# bm20_breakout.net
KiCad netlist of a schematic drawn in EAGLE
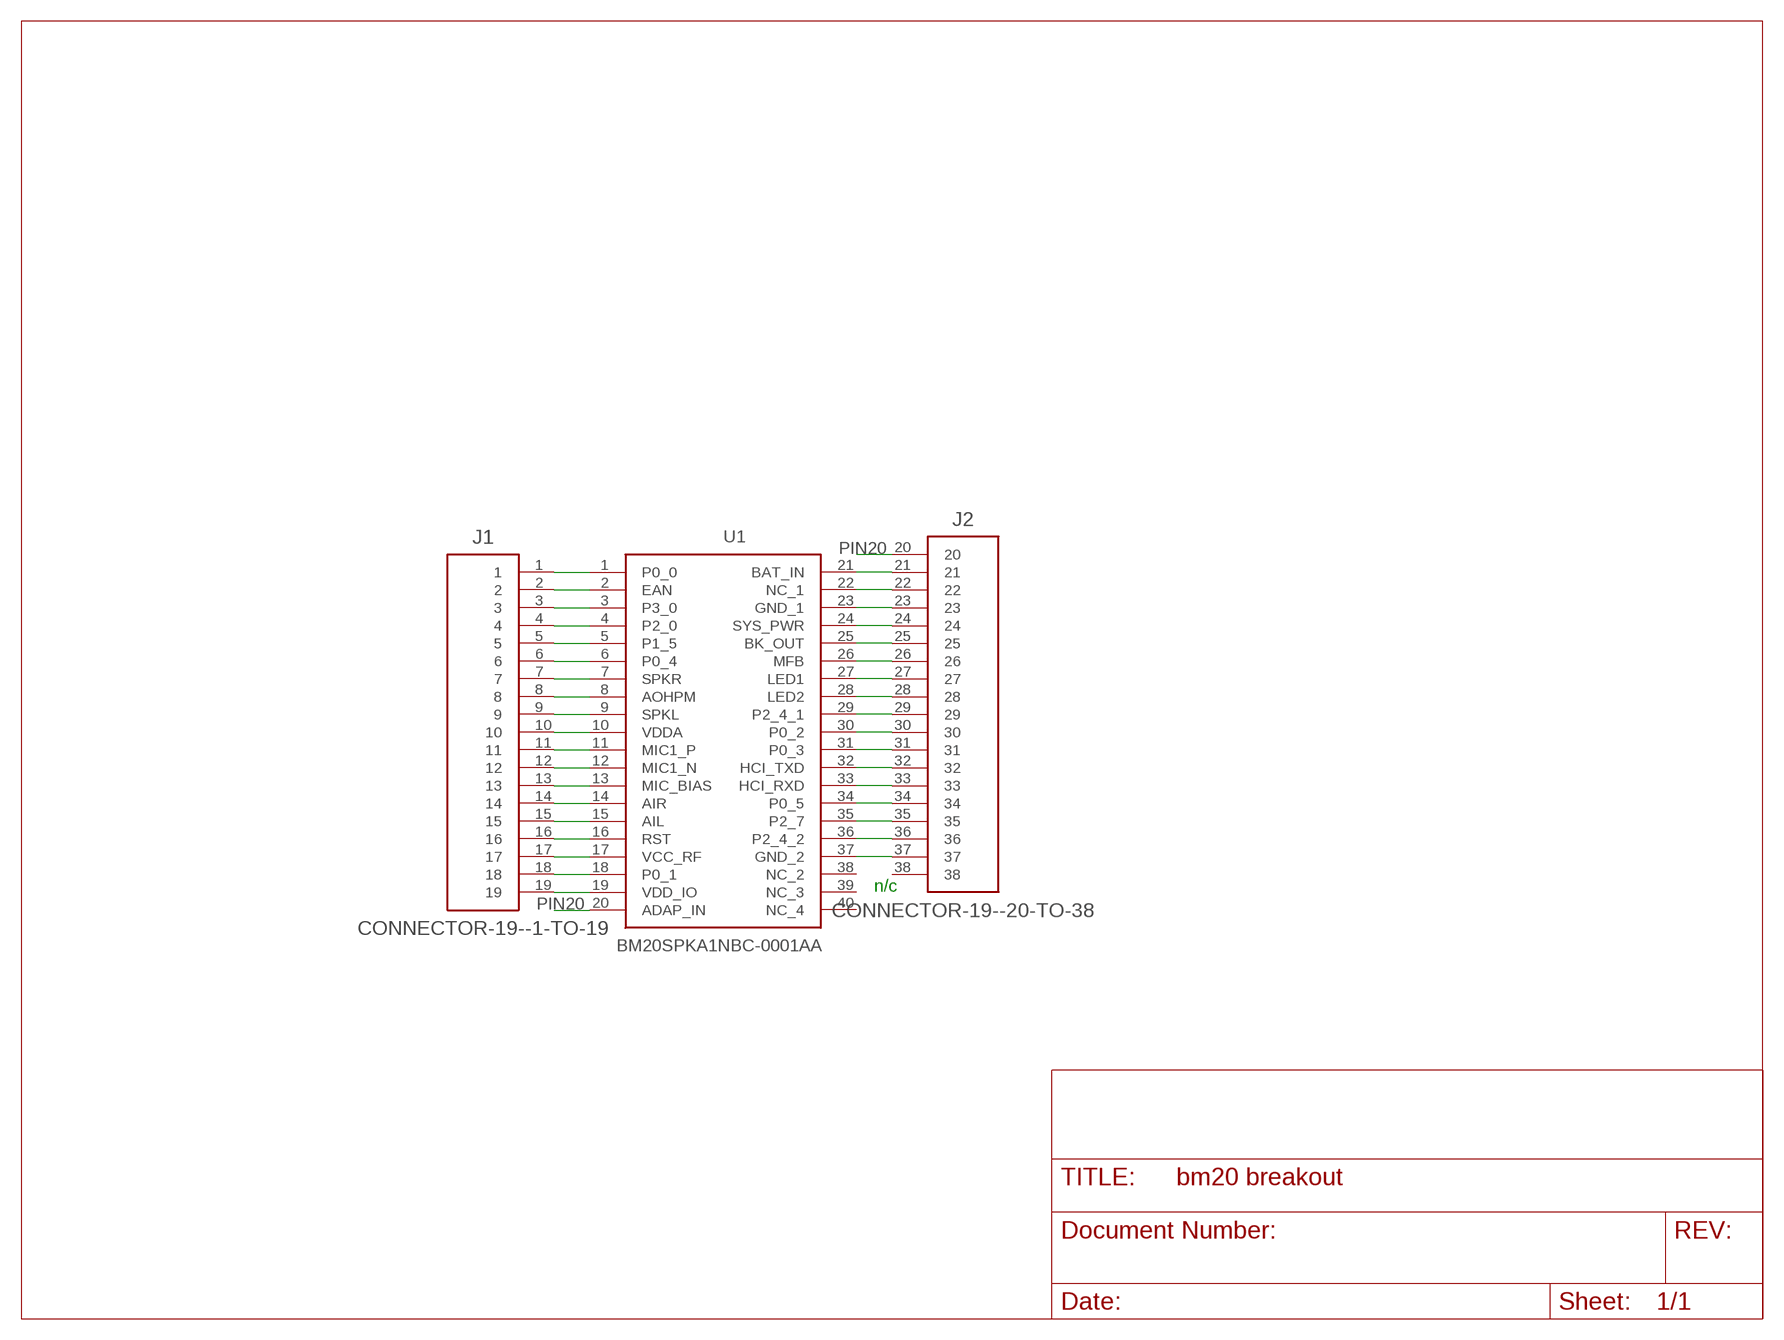
[diagram p0: schematic, sheet 1]

(export (version "E")
  (design (tool "Eeschema 10.0.6"))
  (components
    (comp (ref "J1")
      (value "CONNECTOR-19--1-TO-19")
      (footprint "eagle-import:ESQ-119-XX-XX-S")
      (libsource (lib "eagle-import") (part "CONNECTOR-19--1-TO-19"))
    )
    (comp (ref "J2")
      (value "CONNECTOR-19--20-TO-38")
      (footprint "eagle-import:ESQ-119-XX-XX-S--PIN-1-ROUND")
      (libsource (lib "eagle-import") (part "CONNECTOR-19--20-TO-38"))
    )
    (comp (ref "U1")
      (value "BM20SPKA1NBC-0001AA")
      (footprint "eagle-import:BM20SPKA1NBC0001AA")
      (fields (field (name "MOUSER_PART_NUMBER") "579-SPKA1NBC-0001AA"))
      (libsource (lib "eagle-import") (part "BM20SPKA1NBC-0001AA"))
    )
  )
  (nets
    (net (code "1") (name "/PIN20") (class "Default")
      (node (ref "J2") (pin "20") (pinfunction "20_20") (pintype "bidirectional"))
      (node (ref "U1") (pin "20") (pinfunction "ADAP_IN_20") (pintype "bidirectional"))
    )
    (net (code "2") (name "Net-(U1-AIL)") (class "Default")
      (node (ref "J1") (pin "15") (pinfunction "15_15") (pintype "bidirectional"))
      (node (ref "U1") (pin "15") (pinfunction "AIL_15") (pintype "bidirectional"))
    )
    (net (code "3") (name "Net-(U1-AIR)") (class "Default")
      (node (ref "J1") (pin "14") (pinfunction "14_14") (pintype "bidirectional"))
      (node (ref "U1") (pin "14") (pinfunction "AIR_14") (pintype "bidirectional"))
    )
    (net (code "4") (name "Net-(U1-AOHPM)") (class "Default")
      (node (ref "J1") (pin "8") (pinfunction "8_8") (pintype "bidirectional"))
      (node (ref "U1") (pin "8") (pinfunction "AOHPM_8") (pintype "bidirectional"))
    )
    (net (code "5") (name "Net-(U1-BAT_IN)") (class "Default")
      (node (ref "J2") (pin "21") (pinfunction "21_21") (pintype "bidirectional"))
      (node (ref "U1") (pin "21") (pinfunction "BAT_IN_21") (pintype "bidirectional"))
    )
    (net (code "6") (name "Net-(U1-BK_OUT)") (class "Default")
      (node (ref "J2") (pin "25") (pinfunction "25_25") (pintype "bidirectional"))
      (node (ref "U1") (pin "25") (pinfunction "BK_OUT_25") (pintype "bidirectional"))
    )
    (net (code "7") (name "Net-(U1-EAN)") (class "Default")
      (node (ref "J1") (pin "2") (pinfunction "2_2") (pintype "bidirectional"))
      (node (ref "U1") (pin "2") (pinfunction "EAN_2") (pintype "bidirectional"))
    )
    (net (code "8") (name "Net-(U1-GND_1)") (class "Default")
      (node (ref "J2") (pin "23") (pinfunction "23_23") (pintype "bidirectional"))
      (node (ref "U1") (pin "23") (pinfunction "GND_1_23") (pintype "bidirectional"))
    )
    (net (code "9") (name "Net-(U1-GND_2)") (class "Default")
      (node (ref "J2") (pin "37") (pinfunction "37_37") (pintype "bidirectional"))
      (node (ref "U1") (pin "37") (pinfunction "GND_2_37") (pintype "bidirectional"))
    )
    (net (code "10") (name "Net-(U1-HCI_RXD)") (class "Default")
      (node (ref "J2") (pin "33") (pinfunction "33_33") (pintype "bidirectional"))
      (node (ref "U1") (pin "33") (pinfunction "HCI_RXD_33") (pintype "bidirectional"))
    )
    (net (code "11") (name "Net-(U1-HCI_TXD)") (class "Default")
      (node (ref "J2") (pin "32") (pinfunction "32_32") (pintype "bidirectional"))
      (node (ref "U1") (pin "32") (pinfunction "HCI_TXD_32") (pintype "bidirectional"))
    )
    (net (code "12") (name "Net-(U1-LED1)") (class "Default")
      (node (ref "J2") (pin "27") (pinfunction "27_27") (pintype "bidirectional"))
      (node (ref "U1") (pin "27") (pinfunction "LED1_27") (pintype "bidirectional"))
    )
    (net (code "13") (name "Net-(U1-LED2)") (class "Default")
      (node (ref "J2") (pin "28") (pinfunction "28_28") (pintype "bidirectional"))
      (node (ref "U1") (pin "28") (pinfunction "LED2_28") (pintype "bidirectional"))
    )
    (net (code "14") (name "Net-(U1-MFB)") (class "Default")
      (node (ref "J2") (pin "26") (pinfunction "26_26") (pintype "bidirectional"))
      (node (ref "U1") (pin "26") (pinfunction "MFB_26") (pintype "bidirectional"))
    )
    (net (code "15") (name "Net-(U1-MIC1_N)") (class "Default")
      (node (ref "J1") (pin "12") (pinfunction "12_12") (pintype "bidirectional"))
      (node (ref "U1") (pin "12") (pinfunction "MIC1_N_12") (pintype "bidirectional"))
    )
    (net (code "16") (name "Net-(U1-MIC1_P)") (class "Default")
      (node (ref "J1") (pin "11") (pinfunction "11_11") (pintype "bidirectional"))
      (node (ref "U1") (pin "11") (pinfunction "MIC1_P_11") (pintype "bidirectional"))
    )
    (net (code "17") (name "Net-(U1-MIC_BIAS)") (class "Default")
      (node (ref "J1") (pin "13") (pinfunction "13_13") (pintype "bidirectional"))
      (node (ref "U1") (pin "13") (pinfunction "MIC_BIAS_13") (pintype "bidirectional"))
    )
    (net (code "18") (name "Net-(U1-NC_1)") (class "Default")
      (node (ref "J2") (pin "22") (pinfunction "22_22") (pintype "bidirectional"))
      (node (ref "U1") (pin "22") (pinfunction "NC_1_22") (pintype "bidirectional"))
    )
    (net (code "19") (name "Net-(U1-P0_0)") (class "Default")
      (node (ref "J1") (pin "1") (pinfunction "1_1") (pintype "bidirectional"))
      (node (ref "U1") (pin "1") (pinfunction "P0_0_1") (pintype "bidirectional"))
    )
    (net (code "20") (name "Net-(U1-P0_1)") (class "Default")
      (node (ref "J1") (pin "18") (pinfunction "18_18") (pintype "bidirectional"))
      (node (ref "U1") (pin "18") (pinfunction "P0_1_18") (pintype "bidirectional"))
    )
    (net (code "21") (name "Net-(U1-P0_2)") (class "Default")
      (node (ref "J2") (pin "30") (pinfunction "30_30") (pintype "bidirectional"))
      (node (ref "U1") (pin "30") (pinfunction "P0_2_30") (pintype "bidirectional"))
    )
    (net (code "22") (name "Net-(U1-P0_3)") (class "Default")
      (node (ref "J2") (pin "31") (pinfunction "31_31") (pintype "bidirectional"))
      (node (ref "U1") (pin "31") (pinfunction "P0_3_31") (pintype "bidirectional"))
    )
    (net (code "23") (name "Net-(U1-P0_4)") (class "Default")
      (node (ref "J1") (pin "6") (pinfunction "6_6") (pintype "bidirectional"))
      (node (ref "U1") (pin "6") (pinfunction "P0_4_6") (pintype "bidirectional"))
    )
    (net (code "24") (name "Net-(U1-P0_5)") (class "Default")
      (node (ref "J2") (pin "34") (pinfunction "34_34") (pintype "bidirectional"))
      (node (ref "U1") (pin "34") (pinfunction "P0_5_34") (pintype "bidirectional"))
    )
    (net (code "25") (name "Net-(U1-P1_5)") (class "Default")
      (node (ref "J1") (pin "5") (pinfunction "5_5") (pintype "bidirectional"))
      (node (ref "U1") (pin "5") (pinfunction "P1_5_5") (pintype "bidirectional"))
    )
    (net (code "26") (name "Net-(U1-P2_0)") (class "Default")
      (node (ref "J1") (pin "4") (pinfunction "4_4") (pintype "bidirectional"))
      (node (ref "U1") (pin "4") (pinfunction "P2_0_4") (pintype "bidirectional"))
    )
    (net (code "27") (name "Net-(U1-P2_4_1)") (class "Default")
      (node (ref "J2") (pin "29") (pinfunction "29_29") (pintype "bidirectional"))
      (node (ref "U1") (pin "29") (pinfunction "P2_4_1_29") (pintype "bidirectional"))
    )
    (net (code "28") (name "Net-(U1-P2_4_2)") (class "Default")
      (node (ref "J2") (pin "36") (pinfunction "36_36") (pintype "bidirectional"))
      (node (ref "U1") (pin "36") (pinfunction "P2_4_2_36") (pintype "bidirectional"))
    )
    (net (code "29") (name "Net-(U1-P2_7)") (class "Default")
      (node (ref "J2") (pin "35") (pinfunction "35_35") (pintype "bidirectional"))
      (node (ref "U1") (pin "35") (pinfunction "P2_7_35") (pintype "bidirectional"))
    )
    (net (code "30") (name "Net-(U1-P3_0)") (class "Default")
      (node (ref "J1") (pin "3") (pinfunction "3_3") (pintype "bidirectional"))
      (node (ref "U1") (pin "3") (pinfunction "P3_0_3") (pintype "bidirectional"))
    )
    (net (code "31") (name "Net-(U1-RST)") (class "Default")
      (node (ref "J1") (pin "16") (pinfunction "16_16") (pintype "bidirectional"))
      (node (ref "U1") (pin "16") (pinfunction "RST_16") (pintype "bidirectional"))
    )
    (net (code "32") (name "Net-(U1-SPKL)") (class "Default")
      (node (ref "J1") (pin "9") (pinfunction "9_9") (pintype "bidirectional"))
      (node (ref "U1") (pin "9") (pinfunction "SPKL_9") (pintype "bidirectional"))
    )
    (net (code "33") (name "Net-(U1-SPKR)") (class "Default")
      (node (ref "J1") (pin "7") (pinfunction "7_7") (pintype "bidirectional"))
      (node (ref "U1") (pin "7") (pinfunction "SPKR_7") (pintype "bidirectional"))
    )
    (net (code "34") (name "Net-(U1-SYS_PWR)") (class "Default")
      (node (ref "J2") (pin "24") (pinfunction "24_24") (pintype "bidirectional"))
      (node (ref "U1") (pin "24") (pinfunction "SYS_PWR_24") (pintype "bidirectional"))
    )
    (net (code "35") (name "Net-(U1-VCC_RF)") (class "Default")
      (node (ref "J1") (pin "17") (pinfunction "17_17") (pintype "bidirectional"))
      (node (ref "U1") (pin "17") (pinfunction "VCC_RF_17") (pintype "bidirectional"))
    )
    (net (code "36") (name "Net-(U1-VDDA)") (class "Default")
      (node (ref "J1") (pin "10") (pinfunction "10_10") (pintype "bidirectional"))
      (node (ref "U1") (pin "10") (pinfunction "VDDA_10") (pintype "bidirectional"))
    )
    (net (code "37") (name "Net-(U1-VDD_IO)") (class "Default")
      (node (ref "J1") (pin "19") (pinfunction "19_19") (pintype "bidirectional"))
      (node (ref "U1") (pin "19") (pinfunction "VDD_IO_19") (pintype "bidirectional"))
    )
    (net (code "38") (name "unconnected-(J2-Pad38)") (class "Default")
      (node (ref "J2") (pin "38") (pinfunction "38_38") (pintype "bidirectional"))
    )
    (net (code "39") (name "unconnected-(U1-NC_2-Pad38)") (class "Default")
      (node (ref "U1") (pin "38") (pinfunction "NC_2_38") (pintype "bidirectional"))
    )
    (net (code "40") (name "unconnected-(U1-NC_3-Pad39)") (class "Default")
      (node (ref "U1") (pin "39") (pinfunction "NC_3_39") (pintype "bidirectional"))
    )
    (net (code "41") (name "unconnected-(U1-NC_4-Pad40)") (class "Default")
      (node (ref "U1") (pin "40") (pinfunction "NC_4_40") (pintype "bidirectional"))
    )
  )
)
